# HyperArmBoard.net
KiCad netlist of a schematic drawn in EAGLE
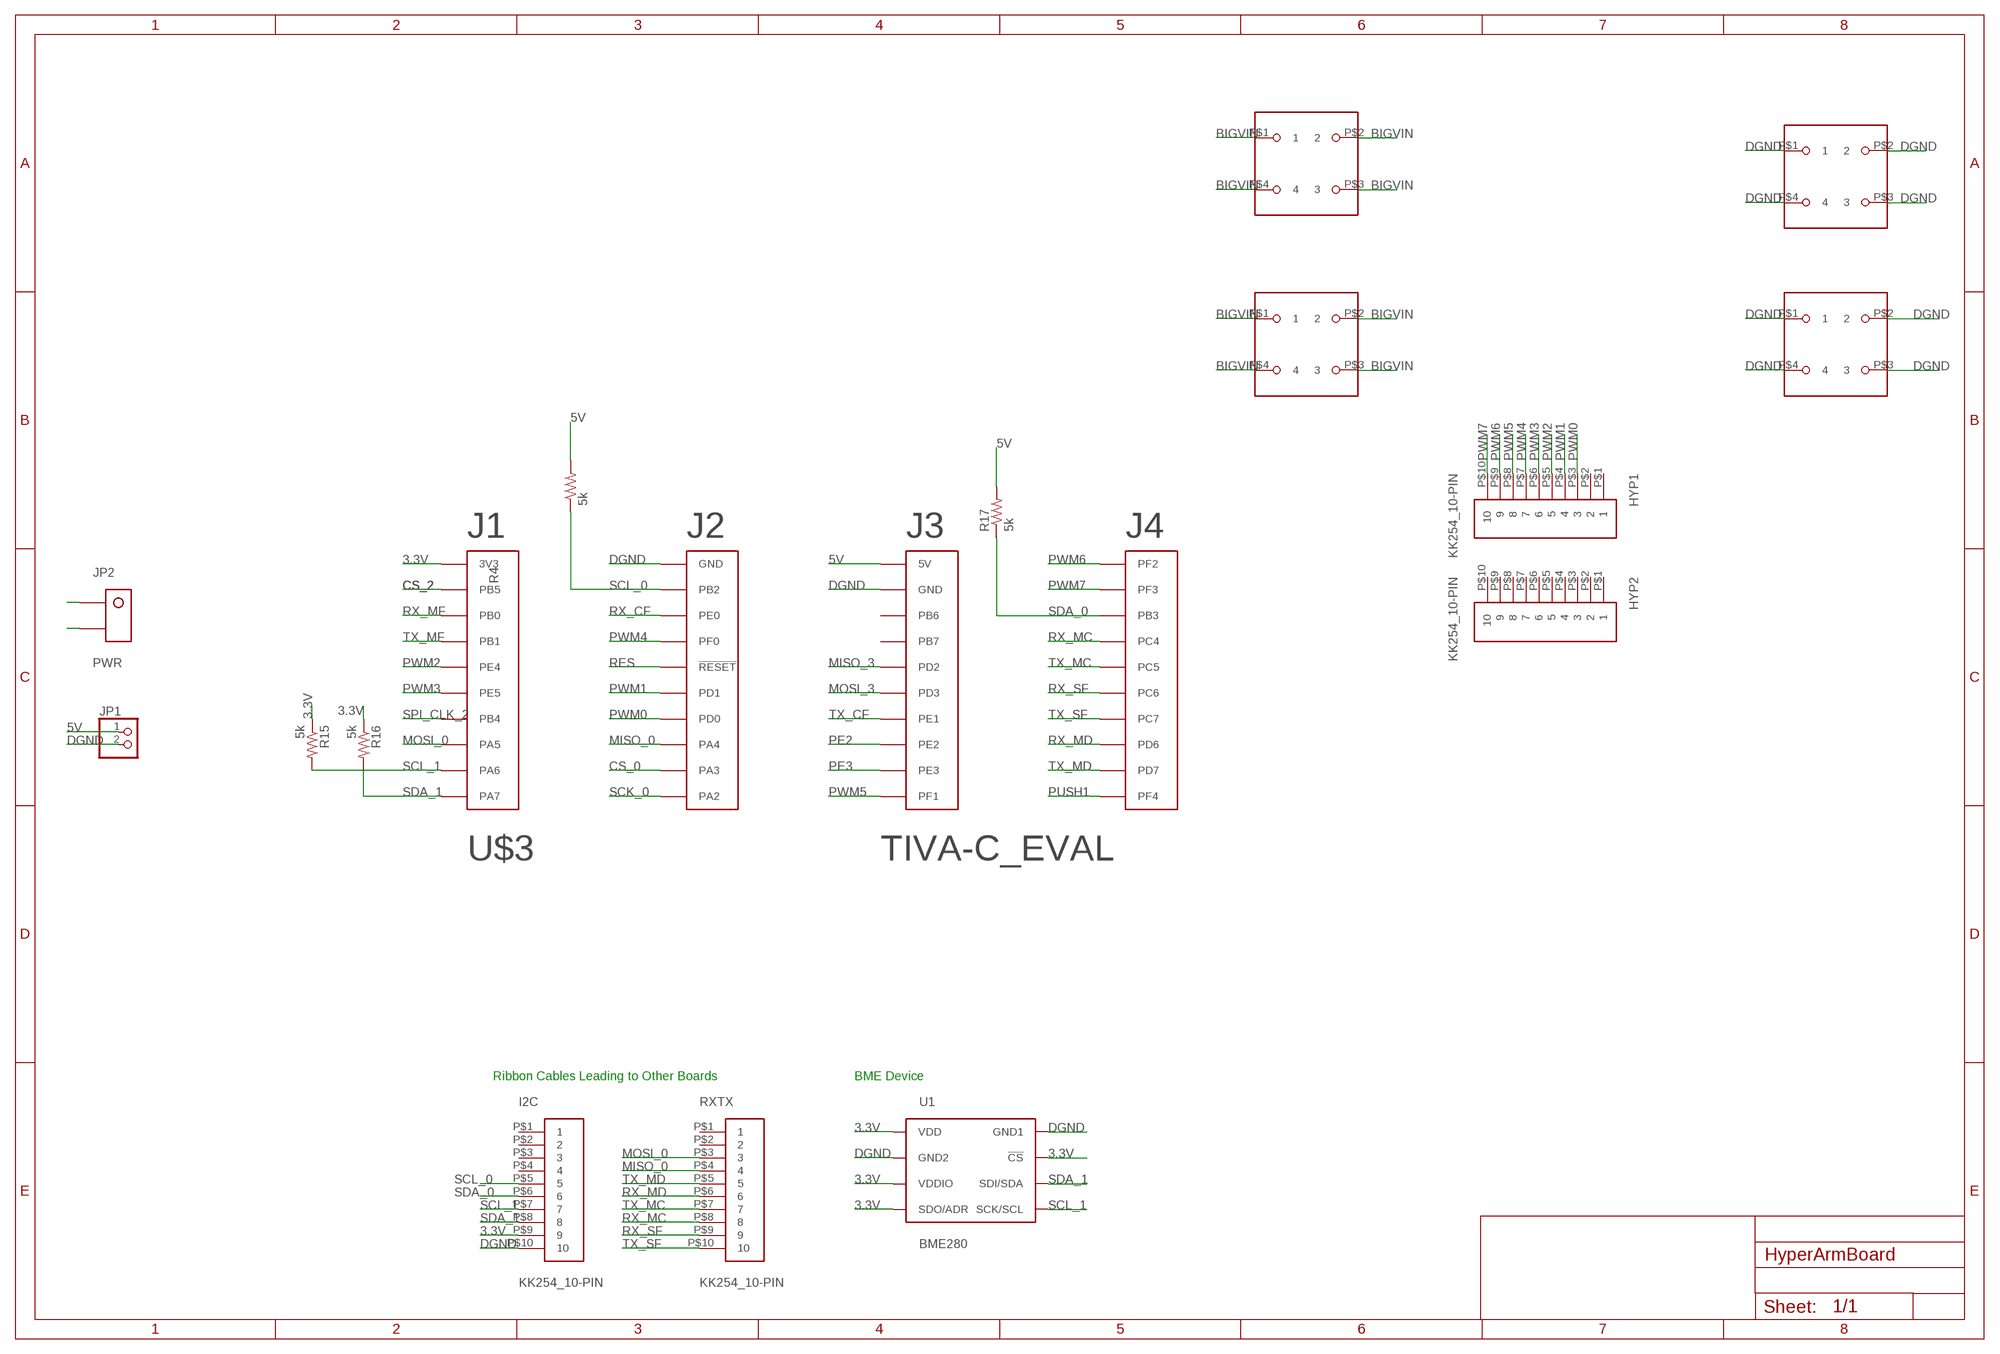
[diagram p0: schematic, sheet 1]

(export (version "E")
  (design (tool "Eeschema 10.0.6"))
  (components
    (comp (ref "HYP1")
      (value "KK254_10-PIN")
      (footprint "eagle-import:KK254_10-PIN")
      (libsource (lib "eagle-import") (part "KK254_10-PIN"))
    )
    (comp (ref "HYP2")
      (value "KK254_10-PIN")
      (footprint "eagle-import:KK254_10-PIN")
      (libsource (lib "eagle-import") (part "KK254_10-PIN"))
    )
    (comp (ref "I2C")
      (value "KK254_10-PIN")
      (footprint "eagle-import:KK254_10-PIN")
      (libsource (lib "eagle-import") (part "KK254_10-PIN"))
    )
    (comp (ref "JP1")
      (value "PINHD-1X2")
      (footprint "eagle-import:1X02")
      (libsource (lib "eagle-import") (part "PINHD-1X2"))
    )
    (comp (ref "JP2")
      (value "PWR")
      (footprint "eagle-import:SUPERSABRE_2CIRCUIT")
      (libsource (lib "eagle-import") (part "2_SUPERSABRE"))
    )
    (comp (ref "R4")
      (value "5k")
      (footprint "eagle-import:R0805")
      (libsource (lib "eagle-import") (part "R-US_R0805"))
    )
    (comp (ref "R15")
      (value "5k")
      (footprint "eagle-import:R0805")
      (libsource (lib "eagle-import") (part "R-US_R0805"))
    )
    (comp (ref "R16")
      (value "5k")
      (footprint "eagle-import:R0805")
      (libsource (lib "eagle-import") (part "R-US_R0805"))
    )
    (comp (ref "R17")
      (value "5k")
      (footprint "eagle-import:R0805")
      (libsource (lib "eagle-import") (part "R-US_R0805"))
    )
    (comp (ref "RXTX")
      (value "KK254_10-PIN")
      (footprint "eagle-import:KK254_10-PIN")
      (libsource (lib "eagle-import") (part "KK254_10-PIN"))
    )
    (comp (ref "U$3")
      (value "TIVA-C_EVAL")
      (footprint "eagle-import:TIVA-C_EVAL")
      (libsource (lib "eagle-import") (part "TIVA-C_EVAL"))
    )
    (comp (ref "U$4")
      (value "BCS-106-L-D-PE-BE")
      (footprint "eagle-import:4-PIN-BIGPOWER")
      (libsource (lib "eagle-import") (part "BCS-106-L-D-PE-BE"))
    )
    (comp (ref "U$5")
      (value "BCS-106-L-D-PE-BE")
      (footprint "eagle-import:4-PIN-BIGPOWER")
      (libsource (lib "eagle-import") (part "BCS-106-L-D-PE-BE"))
    )
    (comp (ref "U$6")
      (value "BCS-106-L-D-PE-BE")
      (footprint "eagle-import:4-PIN-BIGPOWER")
      (libsource (lib "eagle-import") (part "BCS-106-L-D-PE-BE"))
    )
    (comp (ref "U$7")
      (value "BCS-106-L-D-PE-BE")
      (footprint "eagle-import:4-PIN-BIGPOWER")
      (libsource (lib "eagle-import") (part "BCS-106-L-D-PE-BE"))
    )
    (comp (ref "U1")
      (value "BME280")
      (footprint "eagle-import:BME280_LGA")
      (libsource (lib "eagle-import") (part "BME280"))
    )
  )
  (nets
    (net (code "1") (name "/3.3V") (class "Default")
      (node (ref "I2C") (pin "P$9") (pinfunction "9_P$9") (pintype "bidirectional"))
      (node (ref "R15") (pin "1") (pinfunction "1_1") (pintype "passive"))
      (node (ref "R16") (pin "1") (pinfunction "1_1") (pintype "passive"))
      (node (ref "U$3") (pin "1-1") (pinfunction "3V3_1-1") (pintype "bidirectional"))
      (node (ref "U1") (pin "P$2") (pinfunction "~{CS}_P$2") (pintype "bidirectional"))
      (node (ref "U1") (pin "P$5") (pinfunction "SDO/ADR_P$5") (pintype "bidirectional"))
      (node (ref "U1") (pin "P$6") (pinfunction "VDDIO_P$6") (pintype "bidirectional"))
      (node (ref "U1") (pin "P$8") (pinfunction "VDD_P$8") (pintype "bidirectional"))
    )
    (net (code "2") (name "/5V") (class "Default")
      (node (ref "JP1") (pin "1") (pinfunction "1_1") (pintype "passive"))
      (node (ref "R17") (pin "2") (pinfunction "2_2") (pintype "passive"))
      (node (ref "R4") (pin "2") (pinfunction "2_2") (pintype "passive"))
      (node (ref "U$3") (pin "3-1") (pinfunction "5V_3-1") (pintype "bidirectional"))
    )
    (net (code "3") (name "/BIGVIN") (class "Default")
      (node (ref "JP2") (pin "P$1") (pinfunction "P$1_P$1") (pintype "bidirectional"))
      (node (ref "U$4") (pin "P$1") (pinfunction "1_P$1") (pintype "bidirectional"))
      (node (ref "U$4") (pin "P$2") (pinfunction "2_P$2") (pintype "bidirectional"))
      (node (ref "U$4") (pin "P$3") (pinfunction "3_P$3") (pintype "bidirectional"))
      (node (ref "U$4") (pin "P$4") (pinfunction "4_P$4") (pintype "bidirectional"))
      (node (ref "U$5") (pin "P$1") (pinfunction "1_P$1") (pintype "bidirectional"))
      (node (ref "U$5") (pin "P$2") (pinfunction "2_P$2") (pintype "bidirectional"))
      (node (ref "U$5") (pin "P$3") (pinfunction "3_P$3") (pintype "bidirectional"))
      (node (ref "U$5") (pin "P$4") (pinfunction "4_P$4") (pintype "bidirectional"))
    )
    (net (code "4") (name "/CS_0") (class "Default")
      (node (ref "U$3") (pin "2-9") (pinfunction "PA3_2-9") (pintype "bidirectional"))
    )
    (net (code "5") (name "/CS_2") (class "Default")
      (node (ref "U$3") (pin "1-2") (pinfunction "PB5_1-2") (pintype "bidirectional"))
    )
    (net (code "6") (name "/DGND") (class "Default")
      (node (ref "I2C") (pin "P$10") (pinfunction "10_P$10") (pintype "bidirectional"))
      (node (ref "JP1") (pin "2") (pinfunction "2_2") (pintype "passive"))
      (node (ref "JP2") (pin "P$2") (pinfunction "P$2_P$2") (pintype "bidirectional"))
      (node (ref "U$3") (pin "2-1") (pinfunction "GND_2-1") (pintype "bidirectional"))
      (node (ref "U$3") (pin "3-2") (pinfunction "GND_3-2") (pintype "bidirectional"))
      (node (ref "U$6") (pin "P$1") (pinfunction "1_P$1") (pintype "bidirectional"))
      (node (ref "U$6") (pin "P$2") (pinfunction "2_P$2") (pintype "bidirectional"))
      (node (ref "U$6") (pin "P$3") (pinfunction "3_P$3") (pintype "bidirectional"))
      (node (ref "U$6") (pin "P$4") (pinfunction "4_P$4") (pintype "bidirectional"))
      (node (ref "U$7") (pin "P$1") (pinfunction "1_P$1") (pintype "bidirectional"))
      (node (ref "U$7") (pin "P$2") (pinfunction "2_P$2") (pintype "bidirectional"))
      (node (ref "U$7") (pin "P$3") (pinfunction "3_P$3") (pintype "bidirectional"))
      (node (ref "U$7") (pin "P$4") (pinfunction "4_P$4") (pintype "bidirectional"))
      (node (ref "U1") (pin "P$1") (pinfunction "GND1_P$1") (pintype "bidirectional"))
      (node (ref "U1") (pin "P$7") (pinfunction "GND2_P$7") (pintype "bidirectional"))
    )
    (net (code "7") (name "/MISO_0") (class "Default")
      (node (ref "RXTX") (pin "P$4") (pinfunction "4_P$4") (pintype "bidirectional"))
      (node (ref "U$3") (pin "2-8") (pinfunction "PA4_2-8") (pintype "bidirectional"))
    )
    (net (code "8") (name "/MISO_3") (class "Default")
      (node (ref "U$3") (pin "3-5") (pinfunction "PD2_3-5") (pintype "bidirectional"))
    )
    (net (code "9") (name "/MOSI_0") (class "Default")
      (node (ref "RXTX") (pin "P$3") (pinfunction "3_P$3") (pintype "bidirectional"))
      (node (ref "U$3") (pin "1-8") (pinfunction "PA5_1-8") (pintype "bidirectional"))
    )
    (net (code "10") (name "/MOSI_3") (class "Default")
      (node (ref "U$3") (pin "3-6") (pinfunction "PD3_3-6") (pintype "bidirectional"))
    )
    (net (code "11") (name "/PE2") (class "Default")
      (node (ref "U$3") (pin "3-8") (pinfunction "PE2_3-8") (pintype "bidirectional"))
    )
    (net (code "12") (name "/PE3") (class "Default")
      (node (ref "U$3") (pin "3-9") (pinfunction "PE3_3-9") (pintype "bidirectional"))
    )
    (net (code "13") (name "/PUSH1") (class "Default")
      (node (ref "U$3") (pin "4-10") (pinfunction "PF4_4-10") (pintype "bidirectional"))
    )
    (net (code "14") (name "/PWM0") (class "Default")
      (node (ref "HYP1") (pin "P$3") (pinfunction "3_P$3") (pintype "bidirectional"))
      (node (ref "U$3") (pin "2-7") (pinfunction "PD0_2-7") (pintype "bidirectional"))
    )
    (net (code "15") (name "/PWM1") (class "Default")
      (node (ref "HYP1") (pin "P$4") (pinfunction "4_P$4") (pintype "bidirectional"))
      (node (ref "U$3") (pin "2-6") (pinfunction "PD1_2-6") (pintype "bidirectional"))
    )
    (net (code "16") (name "/PWM2") (class "Default")
      (node (ref "HYP1") (pin "P$5") (pinfunction "5_P$5") (pintype "bidirectional"))
      (node (ref "U$3") (pin "1-5") (pinfunction "PE4_1-5") (pintype "bidirectional"))
    )
    (net (code "17") (name "/PWM3") (class "Default")
      (node (ref "HYP1") (pin "P$6") (pinfunction "6_P$6") (pintype "bidirectional"))
      (node (ref "U$3") (pin "1-6") (pinfunction "PE5_1-6") (pintype "bidirectional"))
    )
    (net (code "18") (name "/PWM4") (class "Default")
      (node (ref "HYP1") (pin "P$7") (pinfunction "7_P$7") (pintype "bidirectional"))
      (node (ref "U$3") (pin "2-4") (pinfunction "PF0_2-4") (pintype "bidirectional"))
    )
    (net (code "19") (name "/PWM5") (class "Default")
      (node (ref "HYP1") (pin "P$8") (pinfunction "8_P$8") (pintype "bidirectional"))
      (node (ref "U$3") (pin "3-10") (pinfunction "PF1_3-10") (pintype "bidirectional"))
    )
    (net (code "20") (name "/PWM6") (class "Default")
      (node (ref "HYP1") (pin "P$9") (pinfunction "9_P$9") (pintype "bidirectional"))
      (node (ref "U$3") (pin "4-1") (pinfunction "PF2_4-1") (pintype "bidirectional"))
    )
    (net (code "21") (name "/PWM7") (class "Default")
      (node (ref "HYP1") (pin "P$10") (pinfunction "10_P$10") (pintype "bidirectional"))
      (node (ref "U$3") (pin "4-2") (pinfunction "PF3_4-2") (pintype "bidirectional"))
    )
    (net (code "22") (name "/RES") (class "Default")
      (node (ref "U$3") (pin "2-5") (pinfunction "~{RESET}_2-5") (pintype "bidirectional"))
    )
    (net (code "23") (name "/RX_CF") (class "Default")
      (node (ref "U$3") (pin "2-3") (pinfunction "PE0_2-3") (pintype "bidirectional"))
    )
    (net (code "24") (name "/RX_MC") (class "Default")
      (node (ref "RXTX") (pin "P$8") (pinfunction "8_P$8") (pintype "bidirectional"))
      (node (ref "U$3") (pin "4-4") (pinfunction "PC4_4-4") (pintype "bidirectional"))
    )
    (net (code "25") (name "/RX_MD") (class "Default")
      (node (ref "RXTX") (pin "P$6") (pinfunction "6_P$6") (pintype "bidirectional"))
      (node (ref "U$3") (pin "4-8") (pinfunction "PD6_4-8") (pintype "bidirectional"))
    )
    (net (code "26") (name "/RX_MF") (class "Default")
      (node (ref "U$3") (pin "1-3") (pinfunction "PB0_1-3") (pintype "bidirectional"))
    )
    (net (code "27") (name "/RX_SF") (class "Default")
      (node (ref "RXTX") (pin "P$9") (pinfunction "9_P$9") (pintype "bidirectional"))
      (node (ref "U$3") (pin "4-6") (pinfunction "PC6_4-6") (pintype "bidirectional"))
    )
    (net (code "28") (name "/SCK_0") (class "Default")
      (node (ref "U$3") (pin "2-10") (pinfunction "PA2_2-10") (pintype "bidirectional"))
    )
    (net (code "29") (name "/SCL_0") (class "Default")
      (node (ref "I2C") (pin "P$5") (pinfunction "5_P$5") (pintype "bidirectional"))
      (node (ref "R4") (pin "1") (pinfunction "1_1") (pintype "passive"))
      (node (ref "U$3") (pin "2-2") (pinfunction "PB2_2-2") (pintype "bidirectional"))
    )
    (net (code "30") (name "/SCL_1") (class "Default")
      (node (ref "I2C") (pin "P$7") (pinfunction "7_P$7") (pintype "bidirectional"))
      (node (ref "R15") (pin "2") (pinfunction "2_2") (pintype "passive"))
      (node (ref "U$3") (pin "1-9") (pinfunction "PA6_1-9") (pintype "bidirectional"))
      (node (ref "U1") (pin "P$4") (pinfunction "SCK/SCL_P$4") (pintype "bidirectional"))
    )
    (net (code "31") (name "/SDA_0") (class "Default")
      (node (ref "I2C") (pin "P$6") (pinfunction "6_P$6") (pintype "bidirectional"))
      (node (ref "R17") (pin "1") (pinfunction "1_1") (pintype "passive"))
      (node (ref "U$3") (pin "4-3") (pinfunction "PB3_4-3") (pintype "bidirectional"))
    )
    (net (code "32") (name "/SDA_1") (class "Default")
      (node (ref "I2C") (pin "P$8") (pinfunction "8_P$8") (pintype "bidirectional"))
      (node (ref "R16") (pin "2") (pinfunction "2_2") (pintype "passive"))
      (node (ref "U$3") (pin "1-10") (pinfunction "PA7_1-10") (pintype "bidirectional"))
      (node (ref "U1") (pin "P$3") (pinfunction "SDI/SDA_P$3") (pintype "bidirectional"))
    )
    (net (code "33") (name "/SPI_CLK_2") (class "Default")
      (node (ref "U$3") (pin "1-7") (pinfunction "PB4_1-7") (pintype "bidirectional"))
    )
    (net (code "34") (name "/TX_CF") (class "Default")
      (node (ref "U$3") (pin "3-7") (pinfunction "PE1_3-7") (pintype "bidirectional"))
    )
    (net (code "35") (name "/TX_MC") (class "Default")
      (node (ref "RXTX") (pin "P$7") (pinfunction "7_P$7") (pintype "bidirectional"))
      (node (ref "U$3") (pin "4-5") (pinfunction "PC5_4-5") (pintype "bidirectional"))
    )
    (net (code "36") (name "/TX_MD") (class "Default")
      (node (ref "RXTX") (pin "P$5") (pinfunction "5_P$5") (pintype "bidirectional"))
      (node (ref "U$3") (pin "4-9") (pinfunction "PD7_4-9") (pintype "bidirectional"))
    )
    (net (code "37") (name "/TX_MF") (class "Default")
      (node (ref "U$3") (pin "1-4") (pinfunction "PB1_1-4") (pintype "bidirectional"))
    )
    (net (code "38") (name "/TX_SF") (class "Default")
      (node (ref "RXTX") (pin "P$10") (pinfunction "10_P$10") (pintype "bidirectional"))
      (node (ref "U$3") (pin "4-7") (pinfunction "PC7_4-7") (pintype "bidirectional"))
    )
    (net (code "39") (name "unconnected-(HYP1-1-PadP$1)") (class "Default")
      (node (ref "HYP1") (pin "P$1") (pinfunction "1_P$1") (pintype "bidirectional"))
    )
    (net (code "40") (name "unconnected-(HYP1-2-PadP$2)") (class "Default")
      (node (ref "HYP1") (pin "P$2") (pinfunction "2_P$2") (pintype "bidirectional"))
    )
    (net (code "41") (name "unconnected-(HYP2-1-PadP$1)") (class "Default")
      (node (ref "HYP2") (pin "P$1") (pinfunction "1_P$1") (pintype "bidirectional"))
    )
    (net (code "42") (name "unconnected-(HYP2-2-PadP$2)") (class "Default")
      (node (ref "HYP2") (pin "P$2") (pinfunction "2_P$2") (pintype "bidirectional"))
    )
    (net (code "43") (name "unconnected-(HYP2-3-PadP$3)") (class "Default")
      (node (ref "HYP2") (pin "P$3") (pinfunction "3_P$3") (pintype "bidirectional"))
    )
    (net (code "44") (name "unconnected-(HYP2-4-PadP$4)") (class "Default")
      (node (ref "HYP2") (pin "P$4") (pinfunction "4_P$4") (pintype "bidirectional"))
    )
    (net (code "45") (name "unconnected-(HYP2-5-PadP$5)") (class "Default")
      (node (ref "HYP2") (pin "P$5") (pinfunction "5_P$5") (pintype "bidirectional"))
    )
    (net (code "46") (name "unconnected-(HYP2-6-PadP$6)") (class "Default")
      (node (ref "HYP2") (pin "P$6") (pinfunction "6_P$6") (pintype "bidirectional"))
    )
    (net (code "47") (name "unconnected-(HYP2-7-PadP$7)") (class "Default")
      (node (ref "HYP2") (pin "P$7") (pinfunction "7_P$7") (pintype "bidirectional"))
    )
    (net (code "48") (name "unconnected-(HYP2-8-PadP$8)") (class "Default")
      (node (ref "HYP2") (pin "P$8") (pinfunction "8_P$8") (pintype "bidirectional"))
    )
    (net (code "49") (name "unconnected-(HYP2-9-PadP$9)") (class "Default")
      (node (ref "HYP2") (pin "P$9") (pinfunction "9_P$9") (pintype "bidirectional"))
    )
    (net (code "50") (name "unconnected-(HYP2-10-PadP$10)") (class "Default")
      (node (ref "HYP2") (pin "P$10") (pinfunction "10_P$10") (pintype "bidirectional"))
    )
    (net (code "51") (name "unconnected-(I2C-1-PadP$1)") (class "Default")
      (node (ref "I2C") (pin "P$1") (pinfunction "1_P$1") (pintype "bidirectional"))
    )
    (net (code "52") (name "unconnected-(I2C-2-PadP$2)") (class "Default")
      (node (ref "I2C") (pin "P$2") (pinfunction "2_P$2") (pintype "bidirectional"))
    )
    (net (code "53") (name "unconnected-(I2C-3-PadP$3)") (class "Default")
      (node (ref "I2C") (pin "P$3") (pinfunction "3_P$3") (pintype "bidirectional"))
    )
    (net (code "54") (name "unconnected-(I2C-4-PadP$4)") (class "Default")
      (node (ref "I2C") (pin "P$4") (pinfunction "4_P$4") (pintype "bidirectional"))
    )
    (net (code "55") (name "unconnected-(RXTX-1-PadP$1)") (class "Default")
      (node (ref "RXTX") (pin "P$1") (pinfunction "1_P$1") (pintype "bidirectional"))
    )
    (net (code "56") (name "unconnected-(RXTX-2-PadP$2)") (class "Default")
      (node (ref "RXTX") (pin "P$2") (pinfunction "2_P$2") (pintype "bidirectional"))
    )
    (net (code "57") (name "unconnected-(U$3-PB6-Pad3-3)") (class "Default")
      (node (ref "U$3") (pin "3-3") (pinfunction "PB6_3-3") (pintype "bidirectional"))
    )
    (net (code "58") (name "unconnected-(U$3-PB7-Pad3-4)") (class "Default")
      (node (ref "U$3") (pin "3-4") (pinfunction "PB7_3-4") (pintype "bidirectional"))
    )
  )
)
